# ArticulatedPCBLED.net
KiCad netlist of a schematic drawn in EAGLE
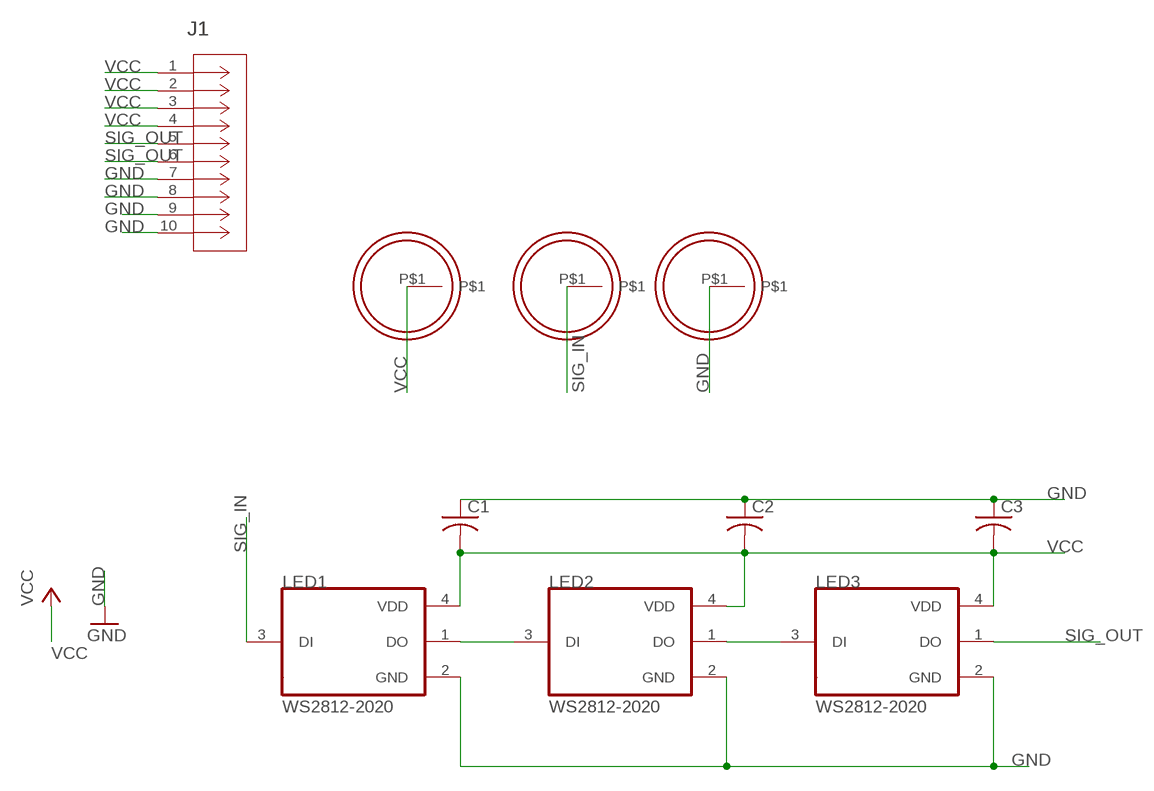
[diagram p0: schematic, sheet 1]

(export (version "E")
  (design (tool "Eeschema 10.0.6"))
  (components
    (comp (ref "C1")
      (value "C-USC0603")
      (footprint "eagle-import:C0603")
      (libsource (lib "eagle-import") (part "C-USC0603"))
    )
    (comp (ref "C2")
      (value "C-USC0603")
      (footprint "eagle-import:C0603")
      (libsource (lib "eagle-import") (part "C-USC0603"))
    )
    (comp (ref "C3")
      (value "C-USC0603")
      (footprint "eagle-import:C0603")
      (libsource (lib "eagle-import") (part "C-USC0603"))
    )
    (comp (ref "J1")
      (value "DF23C-10DP-0.5V(92)")
      (footprint "eagle-import:CONN_DF23C-10DP-0.5V(92)_HIR")
      (fields (field (name "COPYRIGHT") "Copyright (C) 2018 Accelerated Designs. All rights reserved"))
      (libsource (lib "eagle-import") (part "DF23C-10DP-0.5V(92)"))
    )
    (comp (ref "LED1")
      (value "WS2812-2020")
      (footprint "eagle-import:LED_WS2812-2020")
      (fields (field (name "MF") "Worldsemi"))
      (libsource (lib "eagle-import") (part "WS2812-2020"))
    )
    (comp (ref "LED2")
      (value "WS2812-2020")
      (footprint "eagle-import:LED_WS2812-2020")
      (fields (field (name "MF") "Worldsemi"))
      (libsource (lib "eagle-import") (part "WS2812-2020"))
    )
    (comp (ref "LED3")
      (value "WS2812-2020")
      (footprint "eagle-import:LED_WS2812-2020")
      (fields (field (name "MF") "Worldsemi"))
      (libsource (lib "eagle-import") (part "WS2812-2020"))
    )
    (comp (ref "U$2")
      (value "CIRCLE_PAD_17_2_OD")
      (footprint "eagle-import:CIRCLE_PAD_17_2_OD")
      (libsource (lib "eagle-import") (part "CIRCLE_PAD_17_2_OD"))
    )
    (comp (ref "U$3")
      (value "CIRCLE_PAD_8_2_OD")
      (footprint "eagle-import:CIRCLE_PAD_8_2_OD")
      (libsource (lib "eagle-import") (part "CIRCLE_PAD_8_2_OD"))
    )
    (comp (ref "U$4")
      (value "CIRCLE_PAD_12_7_OD")
      (footprint "eagle-import:CIRCLE_PAD_12_7_OD")
      (libsource (lib "eagle-import") (part "CIRCLE_PAD_12_7_OD"))
    )
  )
  (nets
    (net (code "1") (name "/SIG_IN") (class "Default")
      (node (ref "LED1") (pin "3") (pinfunction "DI_3") (pintype "input"))
      (node (ref "U$4") (pin "P$1") (pinfunction "P$1_P$1") (pintype "bidirectional"))
    )
    (net (code "2") (name "/SIG_OUT") (class "Default")
      (node (ref "J1") (pin "5") (pinfunction "5_5") (pintype "passive"))
      (node (ref "J1") (pin "6") (pinfunction "6_6") (pintype "passive"))
      (node (ref "LED3") (pin "1") (pinfunction "DO_1") (pintype "output"))
    )
    (net (code "3") (name "GND") (class "Default")
      (node (ref "C1") (pin "1") (pinfunction "1_1") (pintype "passive"))
      (node (ref "C2") (pin "1") (pinfunction "1_1") (pintype "passive"))
      (node (ref "C3") (pin "1") (pinfunction "1_1") (pintype "passive"))
      (node (ref "J1") (pin "10") (pinfunction "10_10") (pintype "passive"))
      (node (ref "J1") (pin "7") (pinfunction "7_7") (pintype "passive"))
      (node (ref "J1") (pin "8") (pinfunction "8_8") (pintype "passive"))
      (node (ref "J1") (pin "9") (pinfunction "9_9") (pintype "passive"))
      (node (ref "LED1") (pin "2") (pinfunction "GND_2") (pintype "power_in"))
      (node (ref "LED2") (pin "2") (pinfunction "GND_2") (pintype "power_in"))
      (node (ref "LED3") (pin "2") (pinfunction "GND_2") (pintype "power_in"))
      (node (ref "U$2") (pin "P$1") (pinfunction "P$1_P$1") (pintype "bidirectional"))
    )
    (net (code "4") (name "Net-(LED1-DO)") (class "Default")
      (node (ref "LED1") (pin "1") (pinfunction "DO_1") (pintype "output"))
      (node (ref "LED2") (pin "3") (pinfunction "DI_3") (pintype "input"))
    )
    (net (code "5") (name "Net-(LED2-DO)") (class "Default")
      (node (ref "LED2") (pin "1") (pinfunction "DO_1") (pintype "output"))
      (node (ref "LED3") (pin "3") (pinfunction "DI_3") (pintype "input"))
    )
    (net (code "6") (name "VCC") (class "Default")
      (node (ref "C1") (pin "2") (pinfunction "2_2") (pintype "passive"))
      (node (ref "C2") (pin "2") (pinfunction "2_2") (pintype "passive"))
      (node (ref "C3") (pin "2") (pinfunction "2_2") (pintype "passive"))
      (node (ref "J1") (pin "1") (pinfunction "1_1") (pintype "passive"))
      (node (ref "J1") (pin "2") (pinfunction "2_2") (pintype "passive"))
      (node (ref "J1") (pin "3") (pinfunction "3_3") (pintype "passive"))
      (node (ref "J1") (pin "4") (pinfunction "4_4") (pintype "passive"))
      (node (ref "LED1") (pin "4") (pinfunction "VDD_4") (pintype "power_in"))
      (node (ref "LED2") (pin "4") (pinfunction "VDD_4") (pintype "power_in"))
      (node (ref "LED3") (pin "4") (pinfunction "VDD_4") (pintype "power_in"))
      (node (ref "U$3") (pin "P$1") (pinfunction "P$1_P$1") (pintype "bidirectional"))
    )
  )
)
